# S7CAS-PLEIADES-CARTE-MERE_P02_POWER_CARR.net
KiCad netlist of a schematic drawn in Altium Designer
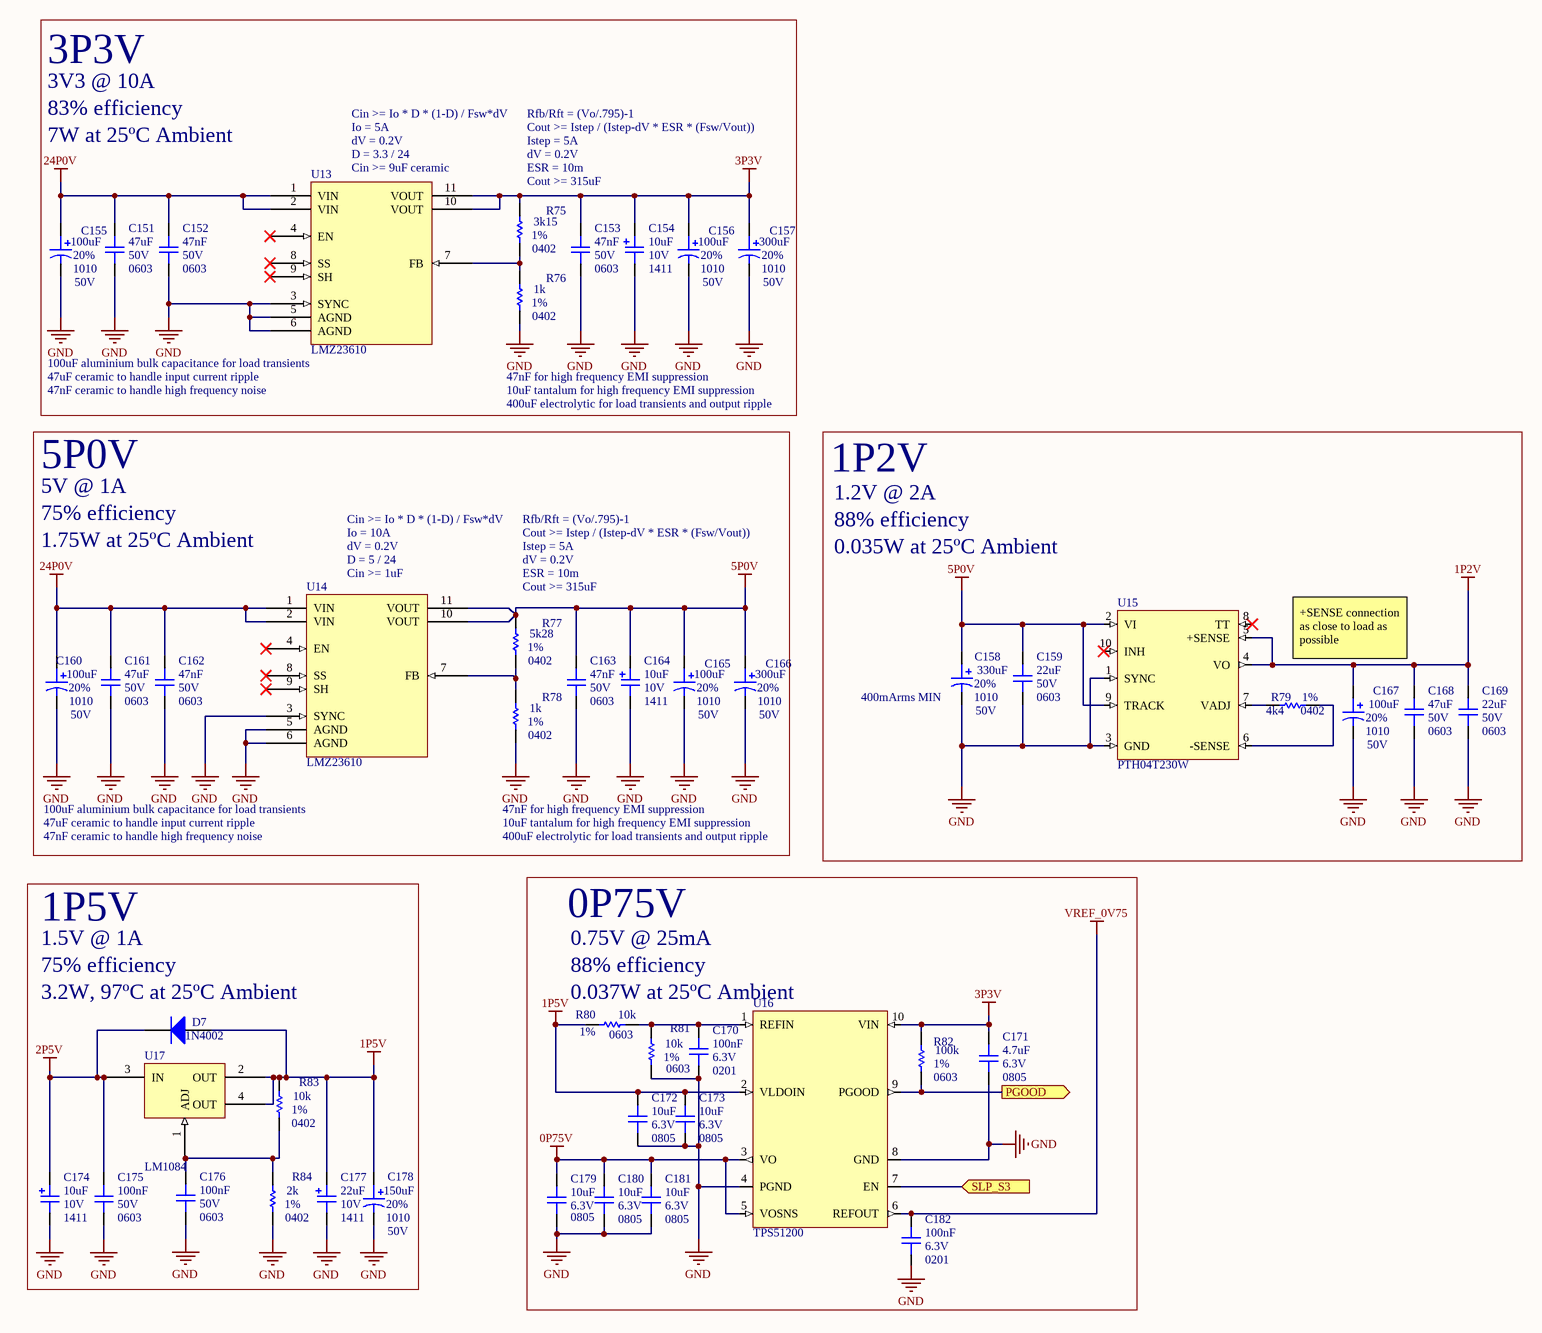
[diagram p0: S7CAS-PLEIADES-CARTE-MERE_P02_POWER_CARRIER.SchDoc]

(export (version "E")
  (design (tool "Eeschema 10.0.6"))
  (components
    (comp (ref "C151")
      (value "47uF")
      (footprint "CAP_0603")
      (description "CAP - 0603")
      (fields
        (field (name "VOLTAGE") "50V")
        (field (name "PACKAGE") "0603")
        (field (name "CREATEDBY") "Jonathan Bouchard")
      )
      (libsource (lib "S7CAS_Lib2019_REV1_00") (part "CAP - 0603"))
    )
    (comp (ref "C152")
      (value "47nF")
      (footprint "CAP_0603")
      (description "CAP - 0603")
      (fields
        (field (name "VOLTAGE") "50V")
        (field (name "PACKAGE") "0603")
        (field (name "CREATEDBY") "Jonathan Bouchard")
      )
      (libsource (lib "S7CAS_Lib2019_REV1_00") (part "CAP - 0603"))
    )
    (comp (ref "C153")
      (value "47nF")
      (footprint "CAP_0603")
      (description "CAP - 0603")
      (fields
        (field (name "VOLTAGE") "50V")
        (field (name "PACKAGE") "0603")
        (field (name "CREATEDBY") "Jonathan Bouchard")
      )
      (libsource (lib "S7CAS_Lib2019_REV1_00") (part "CAP - 0603"))
    )
    (comp (ref "C154")
      (value "10uF")
      (footprint "CAP_TAN_1411(B)")
      (description "CAP - TANTALUM - 1411")
      (fields
        (field (name "VOLTAGE") "10V")
        (field (name "PACKAGE") "1411")
        (field (name "Comment") "CAP - TANTALUM - CASE B")
        (field (name "CREATEDBY") "Jonathan Bouchard")
      )
      (libsource (lib "S7CAS_Lib2019_REV1_00") (part "CAP_TANT_1411(B)"))
    )
    (comp (ref "C155")
      (value "100uF")
      (footprint "CAP_ALU_1010_vishay")
      (description "CAP - ALU 100uF 20% 50V - 1010")
      (fields
        (field (name "MFG") "Vishay Dale")
        (field (name "MFG PART NUMBER") "MAL215099101E3")
        (field (name "VOLTAGE") "50V")
        (field (name "PACKAGE") "1010")
        (field (name "PRECISION") "20%")
        (field (name "CREATEDBY") "Jonathan Bouchard")
      )
      (libsource (lib "S7CAS_Lib2019_REV1_00") (part "CAP_ALU_MAL215099101E3"))
    )
    (comp (ref "C156")
      (value "100uF")
      (footprint "CAP_ALU_1010_vishay")
      (description "CAP - ALU 100uF 20% 50V - 1010")
      (fields
        (field (name "MFG") "Vishay Dale")
        (field (name "MFG PART NUMBER") "MAL215099101E3")
        (field (name "VOLTAGE") "50V")
        (field (name "PACKAGE") "1010")
        (field (name "PRECISION") "20%")
        (field (name "CREATEDBY") "Jonathan Bouchard")
      )
      (libsource (lib "S7CAS_Lib2019_REV1_00") (part "CAP_ALU_MAL215099101E3"))
    )
    (comp (ref "C157")
      (value "300uF")
      (footprint "CAP_ALU_1010_vishay")
      (description "CAP - ALU 100uF 20% 50V - 1010")
      (fields
        (field (name "MFG") "Vishay Dale")
        (field (name "MFG PART NUMBER") "MAL215099101E3")
        (field (name "VOLTAGE") "50V")
        (field (name "PACKAGE") "1010")
        (field (name "PRECISION") "20%")
        (field (name "CREATEDBY") "Jonathan Bouchard")
      )
      (libsource (lib "S7CAS_Lib2019_REV1_00") (part "CAP_ALU_MAL215099101E3"))
    )
    (comp (ref "C158")
      (value "330uF")
      (footprint "CAP_ALU_1010_vishay")
      (description "CAP - ALU 100uF 20% 50V - 1010")
      (fields
        (field (name "MFG") "Vishay Dale")
        (field (name "MFG PART NUMBER") "MAL215099101E3")
        (field (name "VOLTAGE") "50V")
        (field (name "PACKAGE") "1010")
        (field (name "PRECISION") "20%")
        (field (name "CREATEDBY") "Jonathan Bouchard")
      )
      (libsource (lib "S7CAS_Lib2019_REV1_00") (part "CAP_ALU_MAL215099101E3"))
    )
    (comp (ref "C159")
      (value "22uF")
      (footprint "CAP_0603")
      (description "CAP - 0603")
      (fields
        (field (name "VOLTAGE") "50V")
        (field (name "PACKAGE") "0603")
        (field (name "CREATEDBY") "Jonathan Bouchard")
      )
      (libsource (lib "S7CAS_Lib2019_REV1_00") (part "CAP - 0603"))
    )
    (comp (ref "C160")
      (value "100uF")
      (footprint "CAP_ALU_1010_vishay")
      (description "CAP - ALU 100uF 20% 50V - 1010")
      (fields
        (field (name "MFG") "Vishay Dale")
        (field (name "MFG PART NUMBER") "MAL215099101E3")
        (field (name "VOLTAGE") "50V")
        (field (name "PACKAGE") "1010")
        (field (name "PRECISION") "20%")
        (field (name "CREATEDBY") "Jonathan Bouchard")
      )
      (libsource (lib "S7CAS_Lib2019_REV1_00") (part "CAP_ALU_MAL215099101E3"))
    )
    (comp (ref "C161")
      (value "47uF")
      (footprint "CAP_0603")
      (description "CAP - 0603")
      (fields
        (field (name "VOLTAGE") "50V")
        (field (name "PACKAGE") "0603")
        (field (name "CREATEDBY") "Jonathan Bouchard")
      )
      (libsource (lib "S7CAS_Lib2019_REV1_00") (part "CAP - 0603"))
    )
    (comp (ref "C162")
      (value "47nF")
      (footprint "CAP_0603")
      (description "CAP - 0603")
      (fields
        (field (name "VOLTAGE") "50V")
        (field (name "PACKAGE") "0603")
        (field (name "CREATEDBY") "Jonathan Bouchard")
      )
      (libsource (lib "S7CAS_Lib2019_REV1_00") (part "CAP - 0603"))
    )
    (comp (ref "C163")
      (value "47nF")
      (footprint "CAP_0603")
      (description "CAP - 0603")
      (fields
        (field (name "VOLTAGE") "50V")
        (field (name "PACKAGE") "0603")
        (field (name "CREATEDBY") "Jonathan Bouchard")
      )
      (libsource (lib "S7CAS_Lib2019_REV1_00") (part "CAP - 0603"))
    )
    (comp (ref "C164")
      (value "10uF")
      (footprint "CAP_TAN_1411(B)")
      (description "CAP - TANTALUM - 1411")
      (fields
        (field (name "VOLTAGE") "10V")
        (field (name "PACKAGE") "1411")
        (field (name "Comment") "CAP - TANTALUM - CASE B")
        (field (name "CREATEDBY") "Jonathan Bouchard")
      )
      (libsource (lib "S7CAS_Lib2019_REV1_00") (part "CAP_TANT_1411(B)"))
    )
    (comp (ref "C165")
      (value "100uF")
      (footprint "CAP_ALU_1010_vishay")
      (description "CAP - ALU 100uF 20% 50V - 1010")
      (fields
        (field (name "MFG") "Vishay Dale")
        (field (name "MFG PART NUMBER") "MAL215099101E3")
        (field (name "VOLTAGE") "50V")
        (field (name "PACKAGE") "1010")
        (field (name "PRECISION") "20%")
        (field (name "CREATEDBY") "Jonathan Bouchard")
      )
      (libsource (lib "S7CAS_Lib2019_REV1_00") (part "CAP_ALU_MAL215099101E3"))
    )
    (comp (ref "C166")
      (value "300uF")
      (footprint "CAP_ALU_1010_vishay")
      (description "CAP - ALU 100uF 20% 50V - 1010")
      (fields
        (field (name "MFG") "Vishay Dale")
        (field (name "MFG PART NUMBER") "MAL215099101E3")
        (field (name "VOLTAGE") "50V")
        (field (name "PACKAGE") "1010")
        (field (name "PRECISION") "20%")
        (field (name "CREATEDBY") "Jonathan Bouchard")
      )
      (libsource (lib "S7CAS_Lib2019_REV1_00") (part "CAP_ALU_MAL215099101E3"))
    )
    (comp (ref "C167")
      (value "100uF")
      (footprint "CAP_ALU_1010_vishay")
      (description "CAP - ALU 100uF 20% 50V - 1010")
      (fields
        (field (name "MFG") "Vishay Dale")
        (field (name "MFG PART NUMBER") "MAL215099101E3")
        (field (name "VOLTAGE") "50V")
        (field (name "PACKAGE") "1010")
        (field (name "PRECISION") "20%")
        (field (name "CREATEDBY") "Jonathan Bouchard")
      )
      (libsource (lib "S7CAS_Lib2019_REV1_00") (part "CAP_ALU_MAL215099101E3"))
    )
    (comp (ref "C168")
      (value "47uF")
      (footprint "CAP_0603")
      (description "CAP - 0603")
      (fields
        (field (name "VOLTAGE") "50V")
        (field (name "PACKAGE") "0603")
        (field (name "CREATEDBY") "Jonathan Bouchard")
      )
      (libsource (lib "S7CAS_Lib2019_REV1_00") (part "CAP - 0603"))
    )
    (comp (ref "C169")
      (value "22uF")
      (footprint "CAP_0603")
      (description "CAP - 0603")
      (fields
        (field (name "VOLTAGE") "50V")
        (field (name "PACKAGE") "0603")
        (field (name "CREATEDBY") "Jonathan Bouchard")
      )
      (libsource (lib "S7CAS_Lib2019_REV1_00") (part "CAP - 0603"))
    )
    (comp (ref "C170")
      (value "100nF")
      (footprint "CAP_0201")
      (description "CAP - 0201")
      (fields
        (field (name "VOLTAGE") "6.3V")
        (field (name "PACKAGE") "0201")
        (field (name "CREATEDBY") "Jonathan Bouchard")
      )
      (libsource (lib "S7CAS_Lib2019_REV1_00") (part "CAP - 0201"))
    )
    (comp (ref "C171")
      (value "4.7uF")
      (footprint "CAP_0805")
      (description "CAP - 0805")
      (fields
        (field (name "VOLTAGE") "6.3V")
        (field (name "PACKAGE") "0805")
        (field (name "CREATEDBY") "Jonathan Bouchard")
      )
      (libsource (lib "S7CAS_Lib2019_REV1_00") (part "CAP - 0805"))
    )
    (comp (ref "C172")
      (value "10uF")
      (footprint "CAP_0805")
      (description "CAP - 0805")
      (fields
        (field (name "VOLTAGE") "6.3V")
        (field (name "PACKAGE") "0805")
        (field (name "CREATEDBY") "Jonathan Bouchard")
      )
      (libsource (lib "S7CAS_Lib2019_REV1_00") (part "CAP - 0805"))
    )
    (comp (ref "C173")
      (value "10uF")
      (footprint "CAP_0805")
      (description "CAP - 0805")
      (fields
        (field (name "VOLTAGE") "6.3V")
        (field (name "PACKAGE") "0805")
        (field (name "CREATEDBY") "Jonathan Bouchard")
      )
      (libsource (lib "S7CAS_Lib2019_REV1_00") (part "CAP - 0805"))
    )
    (comp (ref "C174")
      (value "10uF")
      (footprint "CAP_TAN_1411(B)")
      (description "CAP - TANTALUM - 1411")
      (fields
        (field (name "VOLTAGE") "10V")
        (field (name "PACKAGE") "1411")
        (field (name "Comment") "CAP - TANTALUM - CASE B")
        (field (name "CREATEDBY") "Jonathan Bouchard")
      )
      (libsource (lib "S7CAS_Lib2019_REV1_00") (part "CAP_TANT_1411(B)"))
    )
    (comp (ref "C175")
      (value "100nF")
      (footprint "CAP_0603")
      (description "CAP - 0603")
      (fields
        (field (name "VOLTAGE") "50V")
        (field (name "PACKAGE") "0603")
        (field (name "CREATEDBY") "Jonathan Bouchard")
      )
      (libsource (lib "S7CAS_Lib2019_REV1_00") (part "CAP - 0603"))
    )
    (comp (ref "C176")
      (value "100nF")
      (footprint "CAP_0603")
      (description "CAP - 0603")
      (fields
        (field (name "VOLTAGE") "50V")
        (field (name "PACKAGE") "0603")
        (field (name "CREATEDBY") "Jonathan Bouchard")
      )
      (libsource (lib "S7CAS_Lib2019_REV1_00") (part "CAP - 0603"))
    )
    (comp (ref "C177")
      (value "22uF")
      (footprint "CAP_TAN_1411(B)")
      (description "CAP - TANTALUM - 1411")
      (fields
        (field (name "VOLTAGE") "10V")
        (field (name "PACKAGE") "1411")
        (field (name "Comment") "CAP - TANTALUM - CASE B")
        (field (name "CREATEDBY") "Jonathan Bouchard")
      )
      (libsource (lib "S7CAS_Lib2019_REV1_00") (part "CAP_TANT_1411(B)"))
    )
    (comp (ref "C178")
      (value "150uF")
      (footprint "CAP_ALU_1010_vishay")
      (description "CAP - ALU 100uF 20% 50V - 1010")
      (fields
        (field (name "MFG") "Vishay Dale")
        (field (name "MFG PART NUMBER") "MAL215099101E3")
        (field (name "VOLTAGE") "50V")
        (field (name "PACKAGE") "1010")
        (field (name "PRECISION") "20%")
        (field (name "CREATEDBY") "Jonathan Bouchard")
      )
      (libsource (lib "S7CAS_Lib2019_REV1_00") (part "CAP_ALU_MAL215099101E3"))
    )
    (comp (ref "C179")
      (value "10uF")
      (footprint "CAP_0805")
      (description "CAP - 0805")
      (fields
        (field (name "VOLTAGE") "6.3V")
        (field (name "PACKAGE") "0805")
        (field (name "CREATEDBY") "Jonathan Bouchard")
      )
      (libsource (lib "S7CAS_Lib2019_REV1_00") (part "CAP - 0805"))
    )
    (comp (ref "C180")
      (value "10uF")
      (footprint "CAP_0805")
      (description "CAP - 0805")
      (fields
        (field (name "VOLTAGE") "6.3V")
        (field (name "PACKAGE") "0805")
        (field (name "CREATEDBY") "Jonathan Bouchard")
      )
      (libsource (lib "S7CAS_Lib2019_REV1_00") (part "CAP - 0805"))
    )
    (comp (ref "C181")
      (value "10uF")
      (footprint "CAP_0805")
      (description "CAP - 0805")
      (fields
        (field (name "VOLTAGE") "6.3V")
        (field (name "PACKAGE") "0805")
        (field (name "CREATEDBY") "Jonathan Bouchard")
      )
      (libsource (lib "S7CAS_Lib2019_REV1_00") (part "CAP - 0805"))
    )
    (comp (ref "C182")
      (value "100nF")
      (footprint "CAP_0201")
      (description "CAP - 0201")
      (fields
        (field (name "VOLTAGE") "6.3V")
        (field (name "PACKAGE") "0201")
        (field (name "CREATEDBY") "Jonathan Bouchard")
      )
      (libsource (lib "S7CAS_Lib2019_REV1_00") (part "CAP - 0201"))
    )
    (comp (ref "D7")
      (value "1N4002")
      (footprint "DO-41")
      (description "1 Amp General Purpose Rectifier")
      (fields (field (name "PUBLISHER") "Altium Limited"))
      (libsource (lib "Miscellaneous Devices") (part "Diode 1N4002"))
    )
    (comp (ref "R75")
      (value "3k15")
      (footprint "RES_0402")
      (description "RES - 0402")
      (fields
        (field (name "VOLTAGE") "50V")
        (field (name "POWER") "1/16W")
        (field (name "PACKAGE") "0402")
        (field (name "PRECISION") "1%")
        (field (name "CREATEDBY") "Jonathan Bouchard")
      )
      (libsource (lib "S7CAS_Lib2019_REV1_00") (part "RES - 0402"))
    )
    (comp (ref "R76")
      (value "1k")
      (footprint "RES_0402")
      (description "RES - 0402")
      (fields
        (field (name "VOLTAGE") "50V")
        (field (name "POWER") "1/16W")
        (field (name "PACKAGE") "0402")
        (field (name "PRECISION") "1%")
        (field (name "CREATEDBY") "Jonathan Bouchard")
      )
      (libsource (lib "S7CAS_Lib2019_REV1_00") (part "RES - 0402"))
    )
    (comp (ref "R77")
      (value "5k28")
      (footprint "RES_0402")
      (description "RES - 0402")
      (fields
        (field (name "VOLTAGE") "50V")
        (field (name "POWER") "1/16W")
        (field (name "PACKAGE") "0402")
        (field (name "PRECISION") "1%")
        (field (name "CREATEDBY") "Jonathan Bouchard")
      )
      (libsource (lib "S7CAS_Lib2019_REV1_00") (part "RES - 0402"))
    )
    (comp (ref "R78")
      (value "1k")
      (footprint "RES_0402")
      (description "RES - 0402")
      (fields
        (field (name "VOLTAGE") "50V")
        (field (name "POWER") "1/16W")
        (field (name "PACKAGE") "0402")
        (field (name "PRECISION") "1%")
        (field (name "CREATEDBY") "Jonathan Bouchard")
      )
      (libsource (lib "S7CAS_Lib2019_REV1_00") (part "RES - 0402"))
    )
    (comp (ref "R79")
      (value "4k4")
      (footprint "RES_0402")
      (description "RES - 0402")
      (fields
        (field (name "VOLTAGE") "50V")
        (field (name "POWER") "1/16W")
        (field (name "PACKAGE") "0402")
        (field (name "PRECISION") "1%")
        (field (name "CREATEDBY") "Jonathan Bouchard")
      )
      (libsource (lib "S7CAS_Lib2019_REV1_00") (part "RES - 0402"))
    )
    (comp (ref "R80")
      (value "10k")
      (footprint "RES_0402")
      (description "RES - 0603")
      (fields
        (field (name "PACKAGE") "0603")
        (field (name "PRECISION") "1%")
        (field (name "CREATEDBY") "Jonathan Bouchard")
      )
      (libsource (lib "S7CAS_Lib2019_REV1_00") (part "RES - 0603"))
    )
    (comp (ref "R81")
      (value "10k")
      (footprint "RES_0402")
      (description "RES - 0603")
      (fields
        (field (name "PACKAGE") "0603")
        (field (name "PRECISION") "1%")
        (field (name "CREATEDBY") "Jonathan Bouchard")
      )
      (libsource (lib "S7CAS_Lib2019_REV1_00") (part "RES - 0603"))
    )
    (comp (ref "R82")
      (value "100k")
      (footprint "RES_0402")
      (description "RES - 0603")
      (fields
        (field (name "PACKAGE") "0603")
        (field (name "PRECISION") "1%")
        (field (name "CREATEDBY") "Jonathan Bouchard")
      )
      (libsource (lib "S7CAS_Lib2019_REV1_00") (part "RES - 0603"))
    )
    (comp (ref "R83")
      (value "10k")
      (footprint "RES_0402")
      (description "RES - 0402")
      (fields
        (field (name "VOLTAGE") "50V")
        (field (name "POWER") "1/16W")
        (field (name "PACKAGE") "0402")
        (field (name "PRECISION") "1%")
        (field (name "CREATEDBY") "Jonathan Bouchard")
      )
      (libsource (lib "S7CAS_Lib2019_REV1_00") (part "RES - 0402"))
    )
    (comp (ref "R84")
      (value "2k")
      (footprint "RES_0402")
      (description "RES - 0402")
      (fields
        (field (name "VOLTAGE") "50V")
        (field (name "POWER") "1/16W")
        (field (name "PACKAGE") "0402")
        (field (name "PRECISION") "1%")
        (field (name "CREATEDBY") "Jonathan Bouchard")
      )
      (libsource (lib "S7CAS_Lib2019_REV1_00") (part "RES - 0402"))
    )
    (comp (ref "U13") (value "LMZ23610") (footprint "NDY0011A") (libsource (lib "lib_JF") (part "LMZ23610")))
    (comp (ref "U14") (value "LMZ23610") (footprint "NDY0011A") (libsource (lib "lib_JF") (part "LMZ23610")))
    (comp (ref "U15")
      (value "PTH04T230W")
      (footprint "PTH04T230W")
      (description "XXX - Description - Package")
      (libsource (lib "lib_JF") (part "PTH04T230W"))
    )
    (comp (ref "U16")
      (value "TPS51200")
      (footprint "VSON-10")
      (description "TPS51200\r\nSink and Source\r\nDDR Termination\r\nRegulator")
      (libsource (lib "lib_Thom") (part "TPS51200"))
    )
    (comp (ref "U17") (value "LM1084") (footprint "DPAK-3") (libsource (lib "lib_JF") (part "LM1084")))
  )
  (nets
    (net (code "1") (name "/PGOOD") (class "Default")
      (node (ref "R82") (pin "1") (pinfunction "1_1") (pintype "passive"))
      (node (ref "U16") (pin "9") (pinfunction "PGOOD_9") (pintype "output"))
    )
    (net (code "2") (name "/SLP_S3") (class "Default")
      (node (ref "U16") (pin "7") (pinfunction "EN_7") (pintype "passive"))
    )
    (net (code "3") (name "0P75V") (class "Default")
      (node (ref "C179") (pin "2") (pinfunction "2_2") (pintype "passive"))
      (node (ref "C180") (pin "2") (pinfunction "2_2") (pintype "passive"))
      (node (ref "C181") (pin "2") (pinfunction "2_2") (pintype "passive"))
      (node (ref "U16") (pin "3") (pinfunction "VO_3") (pintype "output"))
      (node (ref "U16") (pin "5") (pinfunction "VOSNS_5") (pintype "input"))
    )
    (net (code "4") (name "1P2V") (class "Default")
      (node (ref "C167") (pin "1") (pinfunction "1_1") (pintype "passive"))
      (node (ref "C168") (pin "2") (pinfunction "2_2") (pintype "passive"))
      (node (ref "C169") (pin "2") (pinfunction "2_2") (pintype "passive"))
      (node (ref "U15") (pin "4") (pinfunction "VO_4") (pintype "output"))
      (node (ref "U15") (pin "5") (pinfunction "+SENSE_5") (pintype "input"))
    )
    (net (code "5") (name "1P5V") (class "Default")
      (node (ref "C172") (pin "2") (pinfunction "2_2") (pintype "passive"))
      (node (ref "C173") (pin "2") (pinfunction "2_2") (pintype "passive"))
      (node (ref "C177") (pin "2") (pinfunction "2_2") (pintype "passive"))
      (node (ref "C178") (pin "1") (pinfunction "1_1") (pintype "passive"))
      (node (ref "D7") (pin "1") (pinfunction "A_1") (pintype "passive"))
      (node (ref "R80") (pin "2") (pinfunction "2_2") (pintype "passive"))
      (node (ref "R83") (pin "2") (pinfunction "2_2") (pintype "passive"))
      (node (ref "U16") (pin "2") (pinfunction "VLDOIN_2") (pintype "input"))
      (node (ref "U17") (pin "2") (pinfunction "OUT_2") (pintype "power_in"))
      (node (ref "U17") (pin "4") (pinfunction "OUT_4") (pintype "power_in"))
    )
    (net (code "6") (name "2P5V") (class "Default")
      (node (ref "C174") (pin "2") (pinfunction "2_2") (pintype "passive"))
      (node (ref "C175") (pin "2") (pinfunction "2_2") (pintype "passive"))
      (node (ref "D7") (pin "2") (pinfunction "K_2") (pintype "passive"))
      (node (ref "U17") (pin "3") (pinfunction "IN_3") (pintype "power_in"))
    )
    (net (code "7") (name "3P3V") (class "Default")
      (node (ref "C153") (pin "2") (pinfunction "2_2") (pintype "passive"))
      (node (ref "C154") (pin "2") (pinfunction "2_2") (pintype "passive"))
      (node (ref "C156") (pin "1") (pinfunction "1_1") (pintype "passive"))
      (node (ref "C157") (pin "1") (pinfunction "1_1") (pintype "passive"))
      (node (ref "C171") (pin "2") (pinfunction "2_2") (pintype "passive"))
      (node (ref "R75") (pin "2") (pinfunction "2_2") (pintype "passive"))
      (node (ref "R82") (pin "2") (pinfunction "2_2") (pintype "passive"))
      (node (ref "U13") (pin "10") (pinfunction "VOUT_10") (pintype "power_in"))
      (node (ref "U13") (pin "11") (pinfunction "VOUT_11") (pintype "power_in"))
      (node (ref "U16") (pin "10") (pinfunction "VIN_10") (pintype "input"))
    )
    (net (code "8") (name "5P0V") (class "Default")
      (node (ref "C158") (pin "1") (pinfunction "1_1") (pintype "passive"))
      (node (ref "C159") (pin "2") (pinfunction "2_2") (pintype "passive"))
      (node (ref "C163") (pin "2") (pinfunction "2_2") (pintype "passive"))
      (node (ref "C164") (pin "2") (pinfunction "2_2") (pintype "passive"))
      (node (ref "C165") (pin "1") (pinfunction "1_1") (pintype "passive"))
      (node (ref "C166") (pin "1") (pinfunction "1_1") (pintype "passive"))
      (node (ref "R77") (pin "2") (pinfunction "2_2") (pintype "passive"))
      (node (ref "U14") (pin "10") (pinfunction "VOUT_10") (pintype "power_in"))
      (node (ref "U14") (pin "11") (pinfunction "VOUT_11") (pintype "power_in"))
      (node (ref "U15") (pin "2") (pinfunction "VI_2") (pintype "input"))
      (node (ref "U15") (pin "9") (pinfunction "TRACK_9") (pintype "input"))
    )
    (net (code "9") (name "24P0V") (class "Default")
      (node (ref "C151") (pin "2") (pinfunction "2_2") (pintype "passive"))
      (node (ref "C152") (pin "2") (pinfunction "2_2") (pintype "passive"))
      (node (ref "C155") (pin "1") (pinfunction "1_1") (pintype "passive"))
      (node (ref "C160") (pin "1") (pinfunction "1_1") (pintype "passive"))
      (node (ref "C161") (pin "2") (pinfunction "2_2") (pintype "passive"))
      (node (ref "C162") (pin "2") (pinfunction "2_2") (pintype "passive"))
      (node (ref "U13") (pin "1") (pinfunction "VIN_1") (pintype "power_in"))
      (node (ref "U13") (pin "2") (pinfunction "VIN_2") (pintype "power_in"))
      (node (ref "U14") (pin "1") (pinfunction "VIN_1") (pintype "power_in"))
      (node (ref "U14") (pin "2") (pinfunction "VIN_2") (pintype "power_in"))
    )
    (net (code "10") (name "GND") (class "Default")
      (node (ref "C151") (pin "1") (pinfunction "1_1") (pintype "passive"))
      (node (ref "C152") (pin "1") (pinfunction "1_1") (pintype "passive"))
      (node (ref "C153") (pin "1") (pinfunction "1_1") (pintype "passive"))
      (node (ref "C154") (pin "1") (pinfunction "1_1") (pintype "passive"))
      (node (ref "C155") (pin "2") (pinfunction "2_2") (pintype "passive"))
      (node (ref "C156") (pin "2") (pinfunction "2_2") (pintype "passive"))
      (node (ref "C157") (pin "2") (pinfunction "2_2") (pintype "passive"))
      (node (ref "C158") (pin "2") (pinfunction "2_2") (pintype "passive"))
      (node (ref "C159") (pin "1") (pinfunction "1_1") (pintype "passive"))
      (node (ref "C160") (pin "2") (pinfunction "2_2") (pintype "passive"))
      (node (ref "C161") (pin "1") (pinfunction "1_1") (pintype "passive"))
      (node (ref "C162") (pin "1") (pinfunction "1_1") (pintype "passive"))
      (node (ref "C163") (pin "1") (pinfunction "1_1") (pintype "passive"))
      (node (ref "C164") (pin "1") (pinfunction "1_1") (pintype "passive"))
      (node (ref "C165") (pin "2") (pinfunction "2_2") (pintype "passive"))
      (node (ref "C166") (pin "2") (pinfunction "2_2") (pintype "passive"))
      (node (ref "C167") (pin "2") (pinfunction "2_2") (pintype "passive"))
      (node (ref "C168") (pin "1") (pinfunction "1_1") (pintype "passive"))
      (node (ref "C169") (pin "1") (pinfunction "1_1") (pintype "passive"))
      (node (ref "C170") (pin "1") (pinfunction "1_1") (pintype "passive"))
      (node (ref "C171") (pin "1") (pinfunction "1_1") (pintype "passive"))
      (node (ref "C172") (pin "1") (pinfunction "1_1") (pintype "passive"))
      (node (ref "C173") (pin "1") (pinfunction "1_1") (pintype "passive"))
      (node (ref "C174") (pin "1") (pinfunction "1_1") (pintype "passive"))
      (node (ref "C175") (pin "1") (pinfunction "1_1") (pintype "passive"))
      (node (ref "C176") (pin "1") (pinfunction "1_1") (pintype "passive"))
      (node (ref "C177") (pin "1") (pinfunction "1_1") (pintype "passive"))
      (node (ref "C178") (pin "2") (pinfunction "2_2") (pintype "passive"))
      (node (ref "C179") (pin "1") (pinfunction "1_1") (pintype "passive"))
      (node (ref "C180") (pin "1") (pinfunction "1_1") (pintype "passive"))
      (node (ref "C181") (pin "1") (pinfunction "1_1") (pintype "passive"))
      (node (ref "R76") (pin "1") (pinfunction "1_1") (pintype "passive"))
      (node (ref "R78") (pin "1") (pinfunction "1_1") (pintype "passive"))
      (node (ref "R81") (pin "1") (pinfunction "1_1") (pintype "passive"))
      (node (ref "R84") (pin "1") (pinfunction "1_1") (pintype "passive"))
      (node (ref "U13") (pin "3") (pinfunction "SYNC_3") (pintype "input"))
      (node (ref "U13") (pin "5") (pinfunction "AGND_5") (pintype "power_in"))
      (node (ref "U13") (pin "6") (pinfunction "AGND_6") (pintype "power_in"))
      (node (ref "U14") (pin "3") (pinfunction "SYNC_3") (pintype "input"))
      (node (ref "U14") (pin "5") (pinfunction "AGND_5") (pintype "power_in"))
      (node (ref "U14") (pin "6") (pinfunction "AGND_6") (pintype "power_in"))
      (node (ref "U15") (pin "1") (pinfunction "SYNC_1") (pintype "input"))
      (node (ref "U15") (pin "3") (pinfunction "GND_3") (pintype "input"))
      (node (ref "U16") (pin "4") (pinfunction "PGND_4") (pintype "power_in"))
      (node (ref "U16") (pin "8") (pinfunction "GND_8") (pintype "power_in"))
    )
    (net (code "11") (name "Net-(U13-FB)") (class "Default")
      (node (ref "R75") (pin "1") (pinfunction "1_1") (pintype "passive"))
      (node (ref "R76") (pin "2") (pinfunction "2_2") (pintype "passive"))
      (node (ref "U13") (pin "7") (pinfunction "FB_7") (pintype "input"))
    )
    (net (code "12") (name "Net-(U14-FB)") (class "Default")
      (node (ref "R77") (pin "1") (pinfunction "1_1") (pintype "passive"))
      (node (ref "R78") (pin "2") (pinfunction "2_2") (pintype "passive"))
      (node (ref "U14") (pin "7") (pinfunction "FB_7") (pintype "input"))
    )
    (net (code "13") (name "Net-(U15--SENSE)") (class "Default")
      (node (ref "R79") (pin "1") (pinfunction "1_1") (pintype "passive"))
      (node (ref "U15") (pin "6") (pinfunction "-SENSE_6") (pintype "input"))
    )
    (net (code "14") (name "Net-(U15-VADJ)") (class "Default")
      (node (ref "R79") (pin "2") (pinfunction "2_2") (pintype "passive"))
      (node (ref "U15") (pin "7") (pinfunction "VADJ_7") (pintype "input"))
    )
    (net (code "15") (name "Net-(U16-REFIN)") (class "Default")
      (node (ref "C170") (pin "2") (pinfunction "2_2") (pintype "passive"))
      (node (ref "R80") (pin "1") (pinfunction "1_1") (pintype "passive"))
      (node (ref "R81") (pin "2") (pinfunction "2_2") (pintype "passive"))
      (node (ref "U16") (pin "1") (pinfunction "REFIN_1") (pintype "input"))
    )
    (net (code "16") (name "Net-(U17-ADJ)") (class "Default")
      (node (ref "C176") (pin "2") (pinfunction "2_2") (pintype "passive"))
      (node (ref "R83") (pin "1") (pinfunction "1_1") (pintype "passive"))
      (node (ref "R84") (pin "2") (pinfunction "2_2") (pintype "passive"))
      (node (ref "U17") (pin "1") (pinfunction "ADJ_1") (pintype "input"))
    )
    (net (code "17") (name "VREF_0V75") (class "Default")
      (node (ref "C182") (pin "2") (pinfunction "2_2") (pintype "passive"))
      (node (ref "U16") (pin "6") (pinfunction "REFOUT_6") (pintype "output"))
    )
    (net (code "18") (name "unconnected-(C182-Pad1)") (class "Default")
      (node (ref "C182") (pin "1") (pinfunction "1_1") (pintype "passive"))
    )
    (net (code "19") (name "unconnected-(U13-EN-Pad4)") (class "Default")
      (node (ref "U13") (pin "4") (pinfunction "EN_4") (pintype "input+no_connect"))
    )
    (net (code "20") (name "unconnected-(U13-SH-Pad9)") (class "Default")
      (node (ref "U13") (pin "9") (pinfunction "SH_9") (pintype "input+no_connect"))
    )
    (net (code "21") (name "unconnected-(U13-SS-Pad8)") (class "Default")
      (node (ref "U13") (pin "8") (pinfunction "SS_8") (pintype "input+no_connect"))
    )
    (net (code "22") (name "unconnected-(U14-EN-Pad4)") (class "Default")
      (node (ref "U14") (pin "4") (pinfunction "EN_4") (pintype "input+no_connect"))
    )
    (net (code "23") (name "unconnected-(U14-SH-Pad9)") (class "Default")
      (node (ref "U14") (pin "9") (pinfunction "SH_9") (pintype "input+no_connect"))
    )
    (net (code "24") (name "unconnected-(U14-SS-Pad8)") (class "Default")
      (node (ref "U14") (pin "8") (pinfunction "SS_8") (pintype "input+no_connect"))
    )
    (net (code "25") (name "unconnected-(U15-INH-Pad10)") (class "Default")
      (node (ref "U15") (pin "10") (pinfunction "INH_10") (pintype "input+no_connect"))
    )
    (net (code "26") (name "unconnected-(U15-TT-Pad8)") (class "Default")
      (node (ref "U15") (pin "8") (pinfunction "TT_8") (pintype "input+no_connect"))
    )
  )
)
